# config.net
KiCad netlist of a schematic drawn in Altium Designer
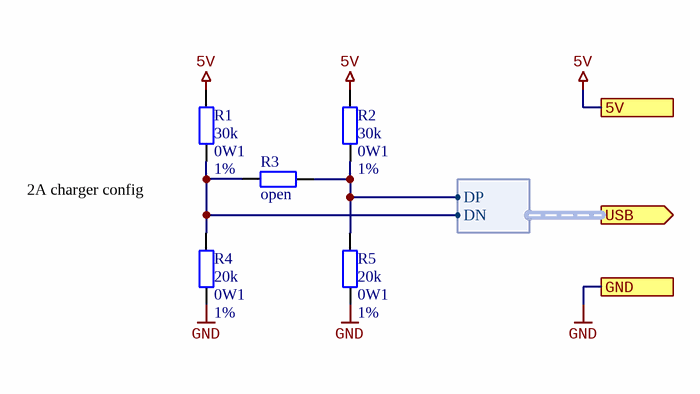
[diagram p0: config.SchDoc]

(export (version "E")
  (design (tool "Eeschema 10.0.6"))
  (components
    (comp (ref "R1")
      (value "30k")
      (footprint "RESC1608N")
      (description "Resistor")
      (fields (field (name "POWER") "0W1") (field (name "TOLERANCE") "1%"))
      (libsource (lib "passives") (part "Resistor"))
    )
    (comp (ref "R2")
      (value "30k")
      (footprint "RESC1608N")
      (description "Resistor")
      (fields (field (name "POWER") "0W1") (field (name "TOLERANCE") "1%"))
      (libsource (lib "passives") (part "Resistor"))
    )
    (comp (ref "R3")
      (value "open")
      (footprint "RESC1608N")
      (description "Resistor")
      (fields (field (name "TOLERANCE") "5%") (field (name "POWER") "0W"))
      (libsource (lib "Discrete") (part "Resistor"))
    )
    (comp (ref "R4")
      (value "20k")
      (footprint "RESC1608N")
      (description "Resistor")
      (fields (field (name "POWER") "0W1") (field (name "TOLERANCE") "1%"))
      (libsource (lib "passives") (part "Resistor"))
    )
    (comp (ref "R5")
      (value "20k")
      (footprint "RESC1608N")
      (description "Resistor")
      (fields (field (name "POWER") "0W1") (field (name "TOLERANCE") "1%"))
      (libsource (lib "passives") (part "Resistor"))
    )
  )
  (nets
    (net (code "3") (name "5V") (class "Default")
      (node (ref "R1") (pin "2") (pinfunction "2_2") (pintype "passive"))
      (node (ref "R2") (pin "2") (pinfunction "2_2") (pintype "passive"))
    )
    (net (code "4") (name "GND") (class "Default")
      (node (ref "R4") (pin "1") (pinfunction "1_1") (pintype "passive"))
      (node (ref "R5") (pin "1") (pinfunction "1_1") (pintype "passive"))
    )
    (net (code "5") (name "Net-(R1-Pad1)") (class "Default")
      (node (ref "R1") (pin "1") (pinfunction "1_1") (pintype "passive"))
      (node (ref "R3") (pin "1") (pinfunction "1_1") (pintype "passive"))
      (node (ref "R4") (pin "2") (pinfunction "2_2") (pintype "passive"))
    )
    (net (code "6") (name "Net-(R2-Pad1)") (class "Default")
      (node (ref "R2") (pin "1") (pinfunction "1_1") (pintype "passive"))
      (node (ref "R3") (pin "2") (pinfunction "2_2") (pintype "passive"))
      (node (ref "R5") (pin "2") (pinfunction "2_2") (pintype "passive"))
    )
  )
)
